# Schematic_motor_driver_v2.net
KiCad netlist of a schematic drawn in Altium Designer
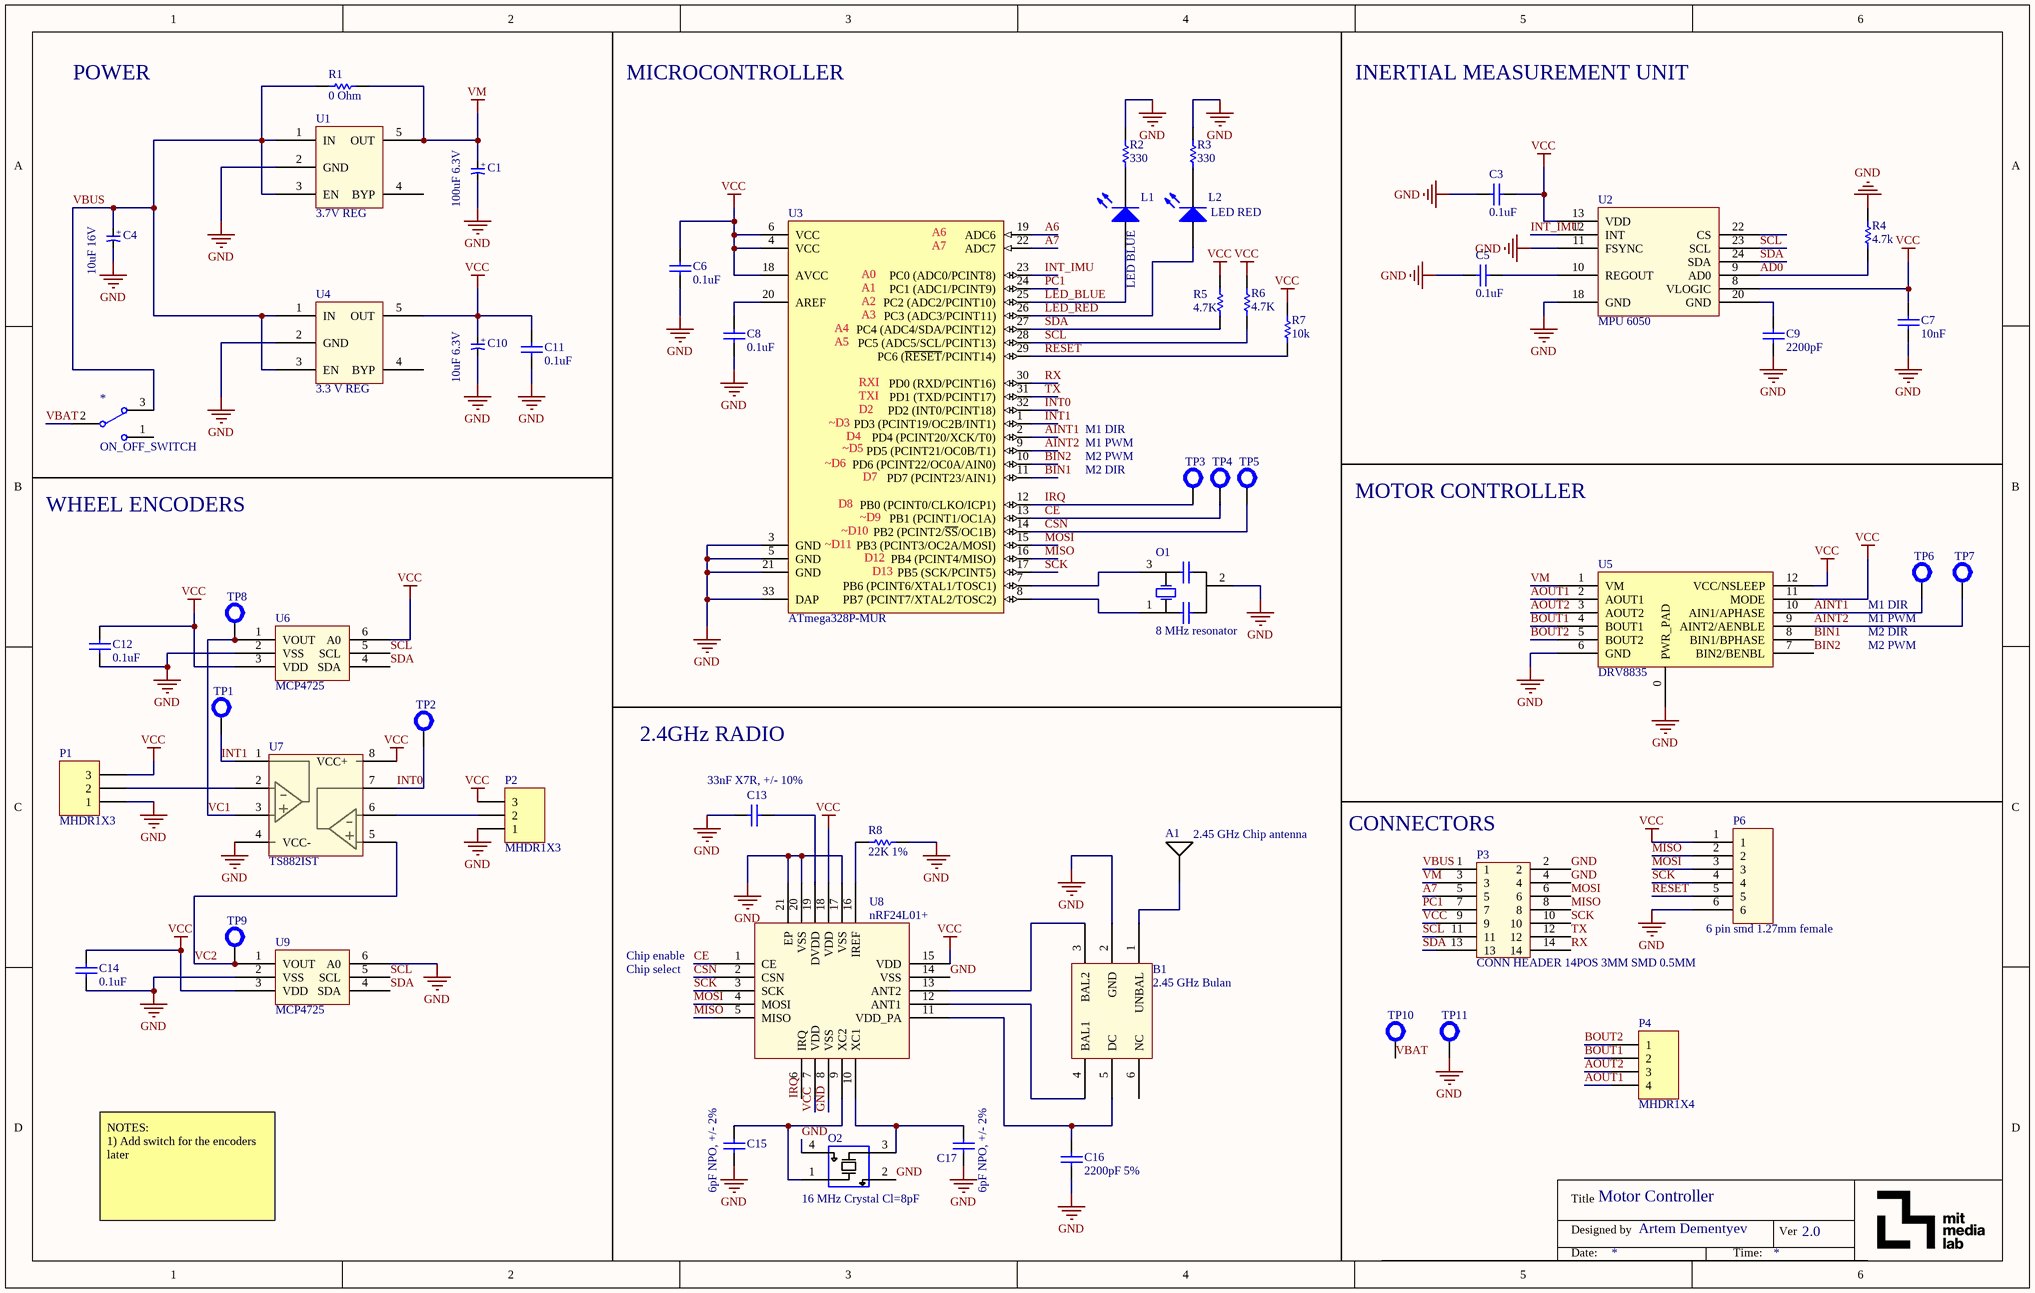
[diagram p0: Schematic_motor_driver_v2.SchDoc]

(export (version "E")
  (design (tool "Eeschema 10.0.6"))
  (components
    (comp (ref "*")
      (value "ON_OFF_SWITCH")
      (footprint "SWTICH_SMD_SIDE")
      (description "SPDT SMD Side Switch")
      (libsource (lib "Artem_Library") (part "ON_OFF_SWITCH"))
    )
    (comp (ref "A1")
      (value "2.45 GHz Chip antenna")
      (footprint "2450AT18A100E")
      (description "for Bluetooth")
      (libsource (lib "Artem_Library") (part "2.45 GHz Chip antenna"))
    )
    (comp (ref "B1")
      (value "2.45 GHz Bulan")
      (footprint "2450BM14A0002")
      (description "for nRF8001 chip")
      (libsource (lib "Artem_Library") (part "2.45 GHz Bulan"))
    )
    (comp (ref "C1")
      (value "100uF 6.3V")
      (footprint "CAP1206")
      (description "Polarised capacitor")
      (libsource (lib "PassiveSMT") (part "Capacitor_pol"))
    )
    (comp (ref "C3")
      (value "0.1uF")
      (footprint "0402W")
      (description "SMD Cap 1206")
      (libsource (lib "Artem_Library") (part "Capacitor"))
    )
    (comp (ref "C4")
      (value "10uF 16V")
      (footprint "CAP0805")
      (description "Polarised capacitor")
      (fields (field (name "DIGIKEY PART NUMBER") "478-8654-1-ND"))
      (libsource (lib "PassiveSMT") (part "Capacitor_pol"))
    )
    (comp (ref "C5")
      (value "0.1uF")
      (footprint "0402W")
      (description "SMD Cap 1206")
      (libsource (lib "Artem_Library") (part "Capacitor"))
    )
    (comp (ref "C6")
      (value "0.1uF")
      (footprint "0402W")
      (description "SMD Cap 1206")
      (libsource (lib "Artem_Library") (part "Capacitor"))
    )
    (comp (ref "C7")
      (value "10nF")
      (footprint "0402W")
      (description "SMD Cap 1206")
      (libsource (lib "Artem_Library") (part "Capacitor"))
    )
    (comp (ref "C8")
      (value "0.1uF")
      (footprint "0402W")
      (description "SMD Cap 1206")
      (libsource (lib "Artem_Library") (part "Capacitor"))
    )
    (comp (ref "C9")
      (value "2200pF")
      (footprint "0402W")
      (description "SMD Cap 1206")
      (libsource (lib "Artem_Library") (part "Capacitor"))
    )
    (comp (ref "C10")
      (value "10uF 6.3V")
      (footprint "0805 TANTALUM")
      (description "Polarised capacitor")
      (fields (field (name "DIGIKEY PART NUMBER") "478-9265-1-ND"))
      (libsource (lib "PassiveSMT") (part "Capacitor_pol"))
    )
    (comp (ref "C11")
      (value "0.1uF")
      (footprint "0603W")
      (description "SMD Cap 1206")
      (libsource (lib "Artem_Library") (part "Capacitor"))
    )
    (comp (ref "C12")
      (value "0.1uF")
      (footprint "0603W")
      (description "SMD Cap 1206")
      (libsource (lib "Artem_Library") (part "Capacitor"))
    )
    (comp (ref "C13")
      (value "33nF X7R, +/- 10%")
      (footprint "0402W")
      (description "SMD Cap 1206")
      (libsource (lib "Artem_Library") (part "Capacitor"))
    )
    (comp (ref "C14")
      (value "0.1uF")
      (footprint "0603W")
      (description "SMD Cap 1206")
      (libsource (lib "Artem_Library") (part "Capacitor"))
    )
    (comp (ref "C15")
      (value "6pF NPO, +/- 2%")
      (footprint "0402W")
      (description "SMD Cap 1206")
      (libsource (lib "Artem_Library") (part "Capacitor"))
    )
    (comp (ref "C16")
      (value "2200pF 5%")
      (footprint "0402W")
      (description "SMD Cap 1206")
      (libsource (lib "Artem_Library") (part "Capacitor"))
    )
    (comp (ref "C17")
      (value "6pF NPO, +/- 2%")
      (footprint "0402W")
      (description "SMD Cap 1206")
      (libsource (lib "Artem_Library") (part "Capacitor"))
    )
    (comp (ref "L1")
      (value "LED BLUE")
      (footprint "0402W")
      (description "LED SMD 1206/0603")
      (libsource (lib "Artem_Library") (part "LED"))
    )
    (comp (ref "L2")
      (value "LED RED")
      (footprint "0402W")
      (description "LED SMD 1206/0603")
      (libsource (lib "Artem_Library") (part "LED"))
    )
    (comp (ref "O1")
      (value "8 MHz resonator")
      (footprint "Resonator SMD")
      (description "Build in caps")
      (libsource (lib "Artem_Library") (part "Resonator SMD"))
    )
    (comp (ref "O2")
      (value "16 MHz Crystal Cl=8pF")
      (footprint "2.5 x 2.0 crystal")
      (description "For BLE use")
      (libsource (lib "Artem_Library") (part "16 MHz Crystal Wireless"))
    )
    (comp (ref "P1")
      (value "MHDR1X3")
      (footprint "MHDR1X3")
      (description "Header, 3-Pin")
      (fields (field (name "PUBLISHER") "Altium Limited"))
      (libsource (lib "Miscellaneous Connectors") (part "MHDR1X3"))
    )
    (comp (ref "P2")
      (value "MHDR1X3")
      (footprint "MHDR1X3")
      (description "Header, 3-Pin")
      (fields (field (name "PUBLISHER") "Altium Limited"))
      (libsource (lib "") (part "MHDR1X3_1"))
    )
    (comp (ref "P3")
      (value "CONN HEADER 14POS 3MM SMD 0.5MM")
      (footprint "DF12 14Pos")
      (fields (field (name "DIGIKEY PART NUMBER") "H11701TR-ND"))
      (libsource (lib "Artem_Library") (part "CONN HEADER 14POS 3MM SMD 0.5MM"))
    )
    (comp (ref "P4")
      (value "MHDR1X4")
      (footprint "MHDR1X4")
      (description "Header, 4-Pin")
      (fields (field (name "PUBLISHER") "Altium Limited"))
      (libsource (lib "Miscellaneous Connectors") (part "MHDR1X4"))
    )
    (comp (ref "P6")
      (value "6 pin smd 1.27mm female")
      (footprint "6pos 1.27mm")
      (libsource (lib "Artem_Library") (part "6 pin smd 1.27mm female"))
    )
    (comp (ref "R1") (value "0 Ohm") (footprint "0603W") (libsource (lib "Artem_Library") (part "Resistor")))
    (comp (ref "R2") (value "330") (footprint "0402W") (libsource (lib "Artem_Library") (part "Resistor")))
    (comp (ref "R3") (value "330") (footprint "0402W") (libsource (lib "Artem_Library") (part "Resistor")))
    (comp (ref "R4") (value "4.7k") (footprint "0402W") (libsource (lib "Artem_Library") (part "Resistor")))
    (comp (ref "R5") (value "4.7K") (footprint "0402W") (libsource (lib "Artem_Library") (part "Resistor")))
    (comp (ref "R6") (value "4.7K") (footprint "0402W") (libsource (lib "Artem_Library") (part "Resistor")))
    (comp (ref "R7") (value "10k") (footprint "0402W") (libsource (lib "Artem_Library") (part "Resistor")))
    (comp (ref "R8") (value "22K 1%") (footprint "0402W") (libsource (lib "Artem_Library") (part "Resistor")))
    (comp (ref "TP1")
      (value "Test point small")
      (footprint "TEST POINT SMD SUPER SMALL")
      (libsource (lib "Artem_Library") (part "Test point small"))
    )
    (comp (ref "TP2")
      (value "Test point small")
      (footprint "TEST POINT SMD SUPER SMALL")
      (libsource (lib "Artem_Library") (part "Test point small"))
    )
    (comp (ref "TP3")
      (value "Test point small")
      (footprint "TEST POINT SMD SUPER SMALL")
      (libsource (lib "Artem_Library") (part "Test point small"))
    )
    (comp (ref "TP4")
      (value "Test point small")
      (footprint "TEST POINT SMD SUPER SMALL")
      (libsource (lib "Artem_Library") (part "Test point small"))
    )
    (comp (ref "TP5")
      (value "Test point small")
      (footprint "TEST POINT SMD SUPER SMALL")
      (libsource (lib "Artem_Library") (part "Test point small"))
    )
    (comp (ref "TP6")
      (value "Test point small")
      (footprint "TEST POINT SMD SUPER SMALL")
      (libsource (lib "Artem_Library") (part "Test point small"))
    )
    (comp (ref "TP7")
      (value "Test point small")
      (footprint "TEST POINT SMD SUPER SMALL")
      (libsource (lib "Artem_Library") (part "Test point small"))
    )
    (comp (ref "TP8")
      (value "Test point small")
      (footprint "TEST POINT SMD SUPER SMALL")
      (libsource (lib "Artem_Library") (part "Test point small"))
    )
    (comp (ref "TP9")
      (value "Test point small")
      (footprint "TEST POINT SMD SUPER SMALL")
      (libsource (lib "Artem_Library") (part "Test point small"))
    )
    (comp (ref "TP10")
      (value "Test point small")
      (footprint "TEST POINT SMD SUPER SMALL")
      (libsource (lib "Artem_Library") (part "Test point small"))
    )
    (comp (ref "TP11")
      (value "Test point small")
      (footprint "TEST POINT SMD SUPER SMALL")
      (libsource (lib "Artem_Library") (part "Test point small"))
    )
    (comp (ref "U1")
      (value "3.7V REG")
      (footprint "SOT-23-5")
      (description "5V LDO SMD")
      (libsource (lib "Artem_Library") (part "MIC5205_VOLTAGE_REG"))
    )
    (comp (ref "U2")
      (value "MPU 6050")
      (footprint "QFN24")
      (description "Gyro / accelerometer combo")
      (libsource (lib "Artem_Library") (part "MPU_6500"))
    )
    (comp (ref "U3")
      (value "ATmega328P-MUR")
      (footprint "32M1-A_M")
      (libsource (lib "Atmel Microcontroller 8-Bit megaAVR") (part "ATmega328P-MUR"))
    )
    (comp (ref "U4")
      (value "3.3 V REG")
      (footprint "SOT-23-5")
      (description "5V LDO SMD")
      (libsource (lib "Artem_Library") (part "MIC5205_VOLTAGE_REG"))
    )
    (comp (ref "U5")
      (value "DRV8835")
      (footprint "WSON-16")
      (fields
        (field (name "DIGIKEY PART NUMBER") "296-30391-1-ND")
        (field (name "MANUFACTURER") "Texas Instruments")
        (field (name "MANUFACTURER PART NUMBER") "DRV8835DSSR")
      )
      (libsource (lib "Artem_Library") (part "DRV8835"))
    )
    (comp (ref "U6")
      (value "MCP4725")
      (footprint "SOT23-6")
      (description "12bit DAC")
      (fields (field (name "DIGIKEY PART NUMBER") "MCP4725A0T-E/CHCT-ND"))
      (libsource (lib "Artem_Library") (part "MCP4725"))
    )
    (comp (ref "U7")
      (value "TS882IST")
      (footprint "MiniS08")
      (description "Rail-to-rail 1.1 V dual comparatpr")
      (fields (field (name "DIGIKEY PART NUMBER") "497-13800-1-ND"))
      (libsource (lib "Artem_Library") (part "TS882IST"))
    )
    (comp (ref "U8")
      (value "nRF24L01+")
      (footprint "QFN20")
      (description "2.4 GHz Radio")
      (fields
        (field (name "DIGIKEY PART NUMBER") "1490-1033-1-ND")
        (field (name "MANUFACTURER PART NUMBER") "nRF24L01P-R")
      )
      (libsource (lib "Artem_Library") (part "nRF24L01+"))
    )
    (comp (ref "U9")
      (value "MCP4725")
      (footprint "SOT23-6")
      (description "12bit DAC")
      (fields (field (name "DIGIKEY PART NUMBER") "MCP4725A0T-E/CHCT-ND"))
      (libsource (lib "Artem_Library") (part "MCP4725"))
    )
  )
  (nets
    (net (code "1") (name "/A6") (class "Default")
      (node (ref "U3") (pin "19") (pinfunction "ADC6_19") (pintype "input"))
    )
    (net (code "2") (name "/A7") (class "Default")
      (node (ref "P3") (pin "5") (pinfunction "5_5") (pintype "passive"))
      (node (ref "U3") (pin "22") (pinfunction "ADC7_22") (pintype "input"))
    )
    (net (code "3") (name "/AD0") (class "Default")
      (node (ref "R4") (pin "1") (pinfunction "1_1") (pintype "passive"))
      (node (ref "U2") (pin "9") (pinfunction "AD0_9") (pintype "passive"))
    )
    (net (code "4") (name "/AINT1") (class "Default")
      (node (ref "TP6") (pin "0") (pinfunction "0_0") (pintype "passive"))
      (node (ref "U3") (pin "2") (pinfunction "PD4_(PCINT20/XCK/T0)_2") (pintype "bidirectional"))
      (node (ref "U5") (pin "10") (pinfunction "AIN1/APHASE_10") (pintype "passive"))
    )
    (net (code "5") (name "/AINT2") (class "Default")
      (node (ref "TP7") (pin "0") (pinfunction "0_0") (pintype "passive"))
      (node (ref "U3") (pin "9") (pinfunction "PD5_(PCINT21/OC0B/T1)_9") (pintype "bidirectional"))
      (node (ref "U5") (pin "9") (pinfunction "AINT2/AENBLE_9") (pintype "passive"))
    )
    (net (code "6") (name "/AOUT1") (class "Default")
      (node (ref "P4") (pin "4") (pinfunction "4_4") (pintype "passive"))
      (node (ref "U5") (pin "2") (pinfunction "AOUT1_2") (pintype "passive"))
    )
    (net (code "7") (name "/AOUT2") (class "Default")
      (node (ref "P4") (pin "3") (pinfunction "3_3") (pintype "passive"))
      (node (ref "U5") (pin "3") (pinfunction "AOUT2_3") (pintype "passive"))
    )
    (net (code "8") (name "/BIN1") (class "Default")
      (node (ref "U3") (pin "11") (pinfunction "PD7_(PCINT23/AIN1)_11") (pintype "bidirectional"))
      (node (ref "U5") (pin "8") (pinfunction "BIN1/BPHASE_8") (pintype "passive"))
    )
    (net (code "9") (name "/BIN2") (class "Default")
      (node (ref "U3") (pin "10") (pinfunction "PD6_(PCINT22/OC0A/AIN0)_10") (pintype "bidirectional"))
      (node (ref "U5") (pin "7") (pinfunction "BIN2/BENBL_7") (pintype "passive"))
    )
    (net (code "10") (name "/BOUT1") (class "Default")
      (node (ref "P4") (pin "2") (pinfunction "2_2") (pintype "passive"))
      (node (ref "U5") (pin "4") (pinfunction "BOUT1_4") (pintype "passive"))
    )
    (net (code "11") (name "/BOUT2") (class "Default")
      (node (ref "P4") (pin "1") (pinfunction "1_1") (pintype "passive"))
      (node (ref "U5") (pin "5") (pinfunction "BOUT2_5") (pintype "passive"))
    )
    (net (code "12") (name "/CE") (class "Default")
      (node (ref "TP4") (pin "0") (pinfunction "0_0") (pintype "passive"))
      (node (ref "U3") (pin "13") (pinfunction "PB1_(PCINT1/OC1A)_13") (pintype "bidirectional"))
      (node (ref "U8") (pin "1") (pinfunction "CE_1") (pintype "passive"))
    )
    (net (code "13") (name "/CSN") (class "Default")
      (node (ref "TP5") (pin "0") (pinfunction "0_0") (pintype "passive"))
      (node (ref "U3") (pin "14") (pinfunction "PB2_(PCINT2/~{SS}/OC1B)_14") (pintype "bidirectional"))
      (node (ref "U8") (pin "2") (pinfunction "CSN_2") (pintype "passive"))
    )
    (net (code "14") (name "/INT0") (class "Default")
      (node (ref "TP2") (pin "0") (pinfunction "0_0") (pintype "passive"))
      (node (ref "U3") (pin "32") (pinfunction "PD2_(INT0/PCINT18)_32") (pintype "bidirectional"))
      (node (ref "U7") (pin "7") (pinfunction "7_7") (pintype "passive"))
    )
    (net (code "15") (name "/INT1") (class "Default")
      (node (ref "TP1") (pin "0") (pinfunction "0_0") (pintype "passive"))
      (node (ref "U3") (pin "1") (pinfunction "PD3_(PCINT19/OC2B/INT1)_1") (pintype "bidirectional"))
      (node (ref "U7") (pin "1") (pinfunction "25_1") (pintype "passive"))
    )
    (net (code "16") (name "/INT_IMU") (class "Default")
      (node (ref "U2") (pin "12") (pinfunction "INT_12") (pintype "passive"))
      (node (ref "U3") (pin "23") (pinfunction "PC0_(ADC0/PCINT8)_23") (pintype "bidirectional"))
    )
    (net (code "17") (name "/IRQ") (class "Default")
      (node (ref "TP3") (pin "0") (pinfunction "0_0") (pintype "passive"))
      (node (ref "U3") (pin "12") (pinfunction "PB0_(PCINT0/CLKO/ICP1)_12") (pintype "bidirectional"))
      (node (ref "U8") (pin "6") (pinfunction "IRQ_6") (pintype "passive"))
    )
    (net (code "18") (name "/LED_BLUE") (class "Default")
      (node (ref "L1") (pin "1") (pinfunction "A_1") (pintype "passive"))
      (node (ref "U3") (pin "25") (pinfunction "PC2_(ADC2/PCINT10)_25") (pintype "bidirectional"))
    )
    (net (code "19") (name "/LED_RED") (class "Default")
      (node (ref "L2") (pin "1") (pinfunction "A_1") (pintype "passive"))
      (node (ref "U3") (pin "26") (pinfunction "PC3_(ADC3/PCINT11)_26") (pintype "bidirectional"))
    )
    (net (code "20") (name "/MISO") (class "Default")
      (node (ref "P3") (pin "8") (pinfunction "8_8") (pintype "passive"))
      (node (ref "P6") (pin "2") (pinfunction "2_2") (pintype "passive"))
      (node (ref "U3") (pin "16") (pinfunction "PB4_(PCINT4/MISO)_16") (pintype "bidirectional"))
      (node (ref "U8") (pin "5") (pinfunction "MISO_5") (pintype "passive"))
    )
    (net (code "21") (name "/MOSI") (class "Default")
      (node (ref "P3") (pin "6") (pinfunction "6_6") (pintype "passive"))
      (node (ref "P6") (pin "3") (pinfunction "3_3") (pintype "passive"))
      (node (ref "U3") (pin "15") (pinfunction "PB3_(PCINT3/OC2A/MOSI)_15") (pintype "bidirectional"))
      (node (ref "U8") (pin "4") (pinfunction "MOSI_4") (pintype "passive"))
    )
    (net (code "22") (name "/PC1") (class "Default")
      (node (ref "P3") (pin "7") (pinfunction "7_7") (pintype "passive"))
      (node (ref "U3") (pin "24") (pinfunction "PC1_(ADC1/PCINT9)_24") (pintype "bidirectional"))
    )
    (net (code "23") (name "/RESET") (class "Default")
      (node (ref "P6") (pin "5") (pinfunction "5_5") (pintype "passive"))
      (node (ref "R7") (pin "1") (pinfunction "1_1") (pintype "passive"))
      (node (ref "U3") (pin "29") (pinfunction "PC6_(~{RESET}/PCINT14)_29") (pintype "bidirectional"))
    )
    (net (code "24") (name "/RX") (class "Default")
      (node (ref "P3") (pin "14") (pinfunction "14_14") (pintype "passive"))
      (node (ref "U3") (pin "30") (pinfunction "PD0_(RXD/PCINT16)_30") (pintype "bidirectional"))
    )
    (net (code "25") (name "/SCK") (class "Default")
      (node (ref "P3") (pin "10") (pinfunction "10_10") (pintype "passive"))
      (node (ref "P6") (pin "4") (pinfunction "4_4") (pintype "passive"))
      (node (ref "U3") (pin "17") (pinfunction "PB5_(SCK/PCINT5)_17") (pintype "bidirectional"))
      (node (ref "U8") (pin "3") (pinfunction "SCK_3") (pintype "passive"))
    )
    (net (code "26") (name "/SCL") (class "Default")
      (node (ref "P3") (pin "11") (pinfunction "11_11") (pintype "passive"))
      (node (ref "R6") (pin "1") (pinfunction "1_1") (pintype "passive"))
      (node (ref "U2") (pin "23") (pinfunction "SCL_23") (pintype "passive"))
      (node (ref "U3") (pin "28") (pinfunction "PC5_(ADC5/SCL/PCINT13)_28") (pintype "bidirectional"))
      (node (ref "U6") (pin "5") (pinfunction "SCL_5") (pintype "passive"))
      (node (ref "U9") (pin "5") (pinfunction "SCL_5") (pintype "passive"))
    )
    (net (code "27") (name "/SDA") (class "Default")
      (node (ref "P3") (pin "13") (pinfunction "13_13") (pintype "passive"))
      (node (ref "R5") (pin "1") (pinfunction "1_1") (pintype "passive"))
      (node (ref "U2") (pin "24") (pinfunction "SDA_24") (pintype "passive"))
      (node (ref "U3") (pin "27") (pinfunction "PC4_(ADC4/SDA/PCINT12)_27") (pintype "bidirectional"))
      (node (ref "U6") (pin "4") (pinfunction "SDA_4") (pintype "passive"))
      (node (ref "U9") (pin "4") (pinfunction "SDA_4") (pintype "passive"))
    )
    (net (code "28") (name "/TX") (class "Default")
      (node (ref "P3") (pin "12") (pinfunction "12_12") (pintype "passive"))
      (node (ref "U3") (pin "31") (pinfunction "PD1_(TXD/PCINT17)_31") (pintype "bidirectional"))
    )
    (net (code "29") (name "/VBAT") (class "Default")
      (node (ref "*") (pin "2") (pinfunction "2_2") (pintype "passive"))
      (node (ref "TP10") (pin "0") (pinfunction "0_0") (pintype "passive"))
    )
    (net (code "30") (name "/VBUS") (class "Default")
      (node (ref "*") (pin "3") (pinfunction "3_3") (pintype "passive"))
      (node (ref "C4") (pin "1") (pinfunction "1_1") (pintype "passive"))
      (node (ref "P3") (pin "1") (pinfunction "1_1") (pintype "passive"))
      (node (ref "R1") (pin "2") (pinfunction "2_2") (pintype "passive"))
      (node (ref "U1") (pin "1") (pinfunction "IN_1") (pintype "passive"))
      (node (ref "U1") (pin "3") (pinfunction "EN_3") (pintype "passive"))
      (node (ref "U4") (pin "1") (pinfunction "IN_1") (pintype "passive"))
      (node (ref "U4") (pin "3") (pinfunction "EN_3") (pintype "passive"))
    )
    (net (code "31") (name "/VC1") (class "Default")
      (node (ref "TP8") (pin "0") (pinfunction "0_0") (pintype "passive"))
      (node (ref "U6") (pin "1") (pinfunction "VOUT_1") (pintype "passive"))
      (node (ref "U7") (pin "3") (pinfunction "3_3") (pintype "passive"))
    )
    (net (code "32") (name "/VC2") (class "Default")
      (node (ref "TP9") (pin "0") (pinfunction "0_0") (pintype "passive"))
      (node (ref "U7") (pin "5") (pinfunction "32_5") (pintype "passive"))
      (node (ref "U9") (pin "1") (pinfunction "VOUT_1") (pintype "passive"))
    )
    (net (code "33") (name "GND") (class "Default")
      (node (ref "B1") (pin "2") (pinfunction "GND_2") (pintype "passive"))
      (node (ref "C1") (pin "2") (pinfunction "2_2") (pintype "passive"))
      (node (ref "C10") (pin "2") (pinfunction "2_2") (pintype "passive"))
      (node (ref "C11") (pin "1") (pinfunction "1_1") (pintype "passive"))
      (node (ref "C12") (pin "1") (pinfunction "1_1") (pintype "passive"))
      (node (ref "C13") (pin "2") (pinfunction "2_2") (pintype "passive"))
      (node (ref "C14") (pin "1") (pinfunction "1_1") (pintype "passive"))
      (node (ref "C15") (pin "1") (pinfunction "1_1") (pintype "passive"))
      (node (ref "C16") (pin "1") (pinfunction "1_1") (pintype "passive"))
      (node (ref "C17") (pin "1") (pinfunction "1_1") (pintype "passive"))
      (node (ref "C3") (pin "2") (pinfunction "2_2") (pintype "passive"))
      (node (ref "C4") (pin "2") (pinfunction "2_2") (pintype "passive"))
      (node (ref "C5") (pin "2") (pinfunction "2_2") (pintype "passive"))
      (node (ref "C6") (pin "1") (pinfunction "1_1") (pintype "passive"))
      (node (ref "C7") (pin "2") (pinfunction "2_2") (pintype "passive"))
      (node (ref "C8") (pin "1") (pinfunction "1_1") (pintype "passive"))
      (node (ref "C9") (pin "2") (pinfunction "2_2") (pintype "passive"))
      (node (ref "O1") (pin "2") (pinfunction "2_2") (pintype "passive"))
      (node (ref "O2") (pin "2") (pinfunction "Gnd_2") (pintype "passive"))
      (node (ref "O2") (pin "4") (pinfunction "Gnd_4") (pintype "passive"))
      (node (ref "P1") (pin "1") (pinfunction "1_1") (pintype "passive"))
      (node (ref "P2") (pin "1") (pinfunction "1_1") (pintype "passive"))
      (node (ref "P3") (pin "2") (pinfunction "2_2") (pintype "passive"))
      (node (ref "P3") (pin "4") (pinfunction "4_4") (pintype "passive"))
      (node (ref "P6") (pin "6") (pinfunction "6_6") (pintype "passive"))
      (node (ref "R2") (pin "1") (pinfunction "1_1") (pintype "passive"))
      (node (ref "R3") (pin "1") (pinfunction "1_1") (pintype "passive"))
      (node (ref "R4") (pin "2") (pinfunction "2_2") (pintype "passive"))
      (node (ref "R8") (pin "1") (pinfunction "1_1") (pintype "passive"))
      (node (ref "TP11") (pin "0") (pinfunction "0_0") (pintype "passive"))
      (node (ref "U1") (pin "2") (pinfunction "GND_2") (pintype "passive"))
      (node (ref "U2") (pin "11") (pinfunction "FSYNC_11") (pintype "passive"))
      (node (ref "U2") (pin "18") (pinfunction "GND_18") (pintype "passive"))
      (node (ref "U3") (pin "21") (pinfunction "GND_21") (pintype "power_in"))
      (node (ref "U3") (pin "3") (pinfunction "GND_3") (pintype "power_in"))
      (node (ref "U3") (pin "33") (pinfunction "DAP_33") (pintype "power_in"))
      (node (ref "U3") (pin "5") (pinfunction "GND_5") (pintype "power_in"))
      (node (ref "U4") (pin "2") (pinfunction "GND_2") (pintype "passive"))
      (node (ref "U5") (pin "0") (pinfunction "PWR_PAD_0") (pintype "passive"))
      (node (ref "U5") (pin "6") (pinfunction "GND_6") (pintype "passive"))
      (node (ref "U6") (pin "2") (pinfunction "VSS_2") (pintype "passive"))
      (node (ref "U7") (pin "4") (pinfunction "VCC-_4") (pintype "passive"))
      (node (ref "U8") (pin "14") (pinfunction "VSS_14") (pintype "passive"))
      (node (ref "U8") (pin "17") (pinfunction "VSS_17") (pintype "passive"))
      (node (ref "U8") (pin "20") (pinfunction "VSS_20") (pintype "passive"))
      (node (ref "U8") (pin "21") (pinfunction "EP_21") (pintype "passive"))
      (node (ref "U8") (pin "8") (pinfunction "VSS_8") (pintype "passive"))
      (node (ref "U9") (pin "2") (pinfunction "VSS_2") (pintype "passive"))
      (node (ref "U9") (pin "6") (pinfunction "A0_6") (pintype "passive"))
    )
    (net (code "34") (name "Net-(B1-BAL1)") (class "Default")
      (node (ref "B1") (pin "4") (pinfunction "BAL1_4") (pintype "passive"))
      (node (ref "U8") (pin "12") (pinfunction "ANT1_12") (pintype "passive"))
    )
    (net (code "35") (name "Net-(B1-BAL2)") (class "Default")
      (node (ref "B1") (pin "3") (pinfunction "BAL2_3") (pintype "passive"))
      (node (ref "U8") (pin "13") (pinfunction "ANT2_13") (pintype "passive"))
    )
    (net (code "36") (name "Net-(B1-DC)") (class "Default")
      (node (ref "B1") (pin "5") (pinfunction "DC_5") (pintype "passive"))
      (node (ref "C16") (pin "2") (pinfunction "2_2") (pintype "passive"))
      (node (ref "U8") (pin "11") (pinfunction "VDD_PA_11") (pintype "passive"))
    )
    (net (code "37") (name "Net-(B1-UNBAL)") (class "Default")
      (node (ref "A1") (pin "1") (pinfunction "1_1") (pintype "passive"))
      (node (ref "B1") (pin "1") (pinfunction "UNBAL_1") (pintype "passive"))
    )
    (net (code "38") (name "Net-(C9-Pad1)") (class "Default")
      (node (ref "C9") (pin "1") (pinfunction "1_1") (pintype "passive"))
      (node (ref "U2") (pin "20") (pinfunction "GND_20") (pintype "passive"))
    )
    (net (code "39") (name "Net-(L1-K)") (class "Default")
      (node (ref "L1") (pin "2") (pinfunction "K_2") (pintype "passive"))
      (node (ref "R2") (pin "2") (pinfunction "2_2") (pintype "passive"))
    )
    (net (code "40") (name "Net-(L2-K)") (class "Default")
      (node (ref "L2") (pin "2") (pinfunction "K_2") (pintype "passive"))
      (node (ref "R3") (pin "2") (pinfunction "2_2") (pintype "passive"))
    )
    (net (code "41") (name "Net-(O2-XIN)") (class "Default")
      (node (ref "C15") (pin "2") (pinfunction "2_2") (pintype "passive"))
      (node (ref "O2") (pin "1") (pinfunction "XIN_1") (pintype "passive"))
      (node (ref "U8") (pin "9") (pinfunction "XC2_9") (pintype "passive"))
    )
    (net (code "42") (name "Net-(O2-XOUT)") (class "Default")
      (node (ref "C17") (pin "2") (pinfunction "2_2") (pintype "passive"))
      (node (ref "O2") (pin "3") (pinfunction "XOUT_3") (pintype "passive"))
      (node (ref "U8") (pin "10") (pinfunction "XC1_10") (pintype "passive"))
    )
    (net (code "43") (name "Net-(P1-Pad2)") (class "Default")
      (node (ref "P1") (pin "2") (pinfunction "2_2") (pintype "passive"))
      (node (ref "U7") (pin "2") (pinfunction "2_2") (pintype "passive"))
    )
    (net (code "44") (name "Net-(P2-Pad2)") (class "Default")
      (node (ref "P2") (pin "2") (pinfunction "2_2") (pintype "passive"))
      (node (ref "U7") (pin "6") (pinfunction "6_6") (pintype "passive"))
    )
    (net (code "45") (name "Net-(U2-REGOUT)") (class "Default")
      (node (ref "C5") (pin "1") (pinfunction "1_1") (pintype "passive"))
      (node (ref "U2") (pin "10") (pinfunction "REGOUT_10") (pintype "passive"))
    )
    (net (code "46") (name "Net-(U3-AREF)") (class "Default")
      (node (ref "C8") (pin "2") (pinfunction "2_2") (pintype "passive"))
      (node (ref "U3") (pin "20") (pinfunction "AREF_20") (pintype "passive"))
    )
    (net (code "47") (name "Net-(U3-PB6_(PCINT6{slash}XTAL1{slash}TOSC1))") (class "Default")
      (node (ref "O1") (pin "3") (pinfunction "3_3") (pintype "passive"))
      (node (ref "U3") (pin "7") (pinfunction "PB6_(PCINT6/XTAL1/TOSC1)_7") (pintype "bidirectional"))
    )
    (net (code "48") (name "Net-(U3-PB7_(PCINT7{slash}XTAL2{slash}TOSC2))") (class "Default")
      (node (ref "O1") (pin "1") (pinfunction "1_1") (pintype "passive"))
      (node (ref "U3") (pin "8") (pinfunction "PB7_(PCINT7/XTAL2/TOSC2)_8") (pintype "bidirectional"))
    )
    (net (code "49") (name "Net-(U8-DVDD)") (class "Default")
      (node (ref "C13") (pin "1") (pinfunction "1_1") (pintype "passive"))
      (node (ref "U8") (pin "19") (pinfunction "DVDD_19") (pintype "passive"))
    )
    (net (code "50") (name "Net-(U8-IREF)") (class "Default")
      (node (ref "R8") (pin "2") (pinfunction "2_2") (pintype "passive"))
      (node (ref "U8") (pin "16") (pinfunction "IREF_16") (pintype "passive"))
    )
    (net (code "51") (name "VCC") (class "Default")
      (node (ref "C10") (pin "1") (pinfunction "1_1") (pintype "passive"))
      (node (ref "C11") (pin "2") (pinfunction "2_2") (pintype "passive"))
      (node (ref "C12") (pin "2") (pinfunction "2_2") (pintype "passive"))
      (node (ref "C14") (pin "2") (pinfunction "2_2") (pintype "passive"))
      (node (ref "C3") (pin "1") (pinfunction "1_1") (pintype "passive"))
      (node (ref "C6") (pin "2") (pinfunction "2_2") (pintype "passive"))
      (node (ref "C7") (pin "1") (pinfunction "1_1") (pintype "passive"))
      (node (ref "P1") (pin "3") (pinfunction "3_3") (pintype "passive"))
      (node (ref "P2") (pin "3") (pinfunction "3_3") (pintype "passive"))
      (node (ref "P3") (pin "9") (pinfunction "9_9") (pintype "passive"))
      (node (ref "P6") (pin "1") (pinfunction "1_1") (pintype "passive"))
      (node (ref "R5") (pin "2") (pinfunction "2_2") (pintype "passive"))
      (node (ref "R6") (pin "2") (pinfunction "2_2") (pintype "passive"))
      (node (ref "R7") (pin "2") (pinfunction "2_2") (pintype "passive"))
      (node (ref "U2") (pin "13") (pinfunction "VDD_13") (pintype "passive"))
      (node (ref "U2") (pin "8") (pinfunction "VLOGIC_8") (pintype "passive"))
      (node (ref "U3") (pin "18") (pinfunction "AVCC_18") (pintype "power_in"))
      (node (ref "U3") (pin "4") (pinfunction "VCC_4") (pintype "power_in"))
      (node (ref "U3") (pin "6") (pinfunction "VCC_6") (pintype "power_in"))
      (node (ref "U4") (pin "5") (pinfunction "OUT_5") (pintype "passive"))
      (node (ref "U5") (pin "11") (pinfunction "MODE_11") (pintype "passive"))
      (node (ref "U5") (pin "12") (pinfunction "VCC/NSLEEP_12") (pintype "passive"))
      (node (ref "U6") (pin "3") (pinfunction "VDD_3") (pintype "passive"))
      (node (ref "U6") (pin "6") (pinfunction "A0_6") (pintype "passive"))
      (node (ref "U7") (pin "8") (pinfunction "VCC+_8") (pintype "passive"))
      (node (ref "U8") (pin "15") (pinfunction "VDD_15") (pintype "passive"))
      (node (ref "U8") (pin "18") (pinfunction "VDD_18") (pintype "passive"))
      (node (ref "U8") (pin "7") (pinfunction "VDD_7") (pintype "passive"))
      (node (ref "U9") (pin "3") (pinfunction "VDD_3") (pintype "passive"))
    )
    (net (code "52") (name "VM") (class "Default")
      (node (ref "C1") (pin "1") (pinfunction "1_1") (pintype "passive"))
      (node (ref "P3") (pin "3") (pinfunction "3_3") (pintype "passive"))
      (node (ref "R1") (pin "1") (pinfunction "1_1") (pintype "passive"))
      (node (ref "U1") (pin "5") (pinfunction "OUT_5") (pintype "passive"))
      (node (ref "U5") (pin "1") (pinfunction "VM_1") (pintype "passive"))
    )
    (net (code "53") (name "unconnected-(*-Pad1)") (class "Default")
      (node (ref "*") (pin "1") (pinfunction "1_1") (pintype "passive"))
    )
    (net (code "54") (name "unconnected-(B1-NC-Pad6)") (class "Default")
      (node (ref "B1") (pin "6") (pinfunction "NC_6") (pintype "passive"))
    )
    (net (code "55") (name "unconnected-(U1-BYP-Pad4)") (class "Default")
      (node (ref "U1") (pin "4") (pinfunction "BYP_4") (pintype "passive"))
    )
    (net (code "56") (name "unconnected-(U2-CS-Pad22)") (class "Default")
      (node (ref "U2") (pin "22") (pinfunction "CS_22") (pintype "passive"))
    )
    (net (code "57") (name "unconnected-(U4-BYP-Pad4)") (class "Default")
      (node (ref "U4") (pin "4") (pinfunction "BYP_4") (pintype "passive"))
    )
  )
)
